# controlnode.net
KiCad netlist of a schematic drawn in EAGLE
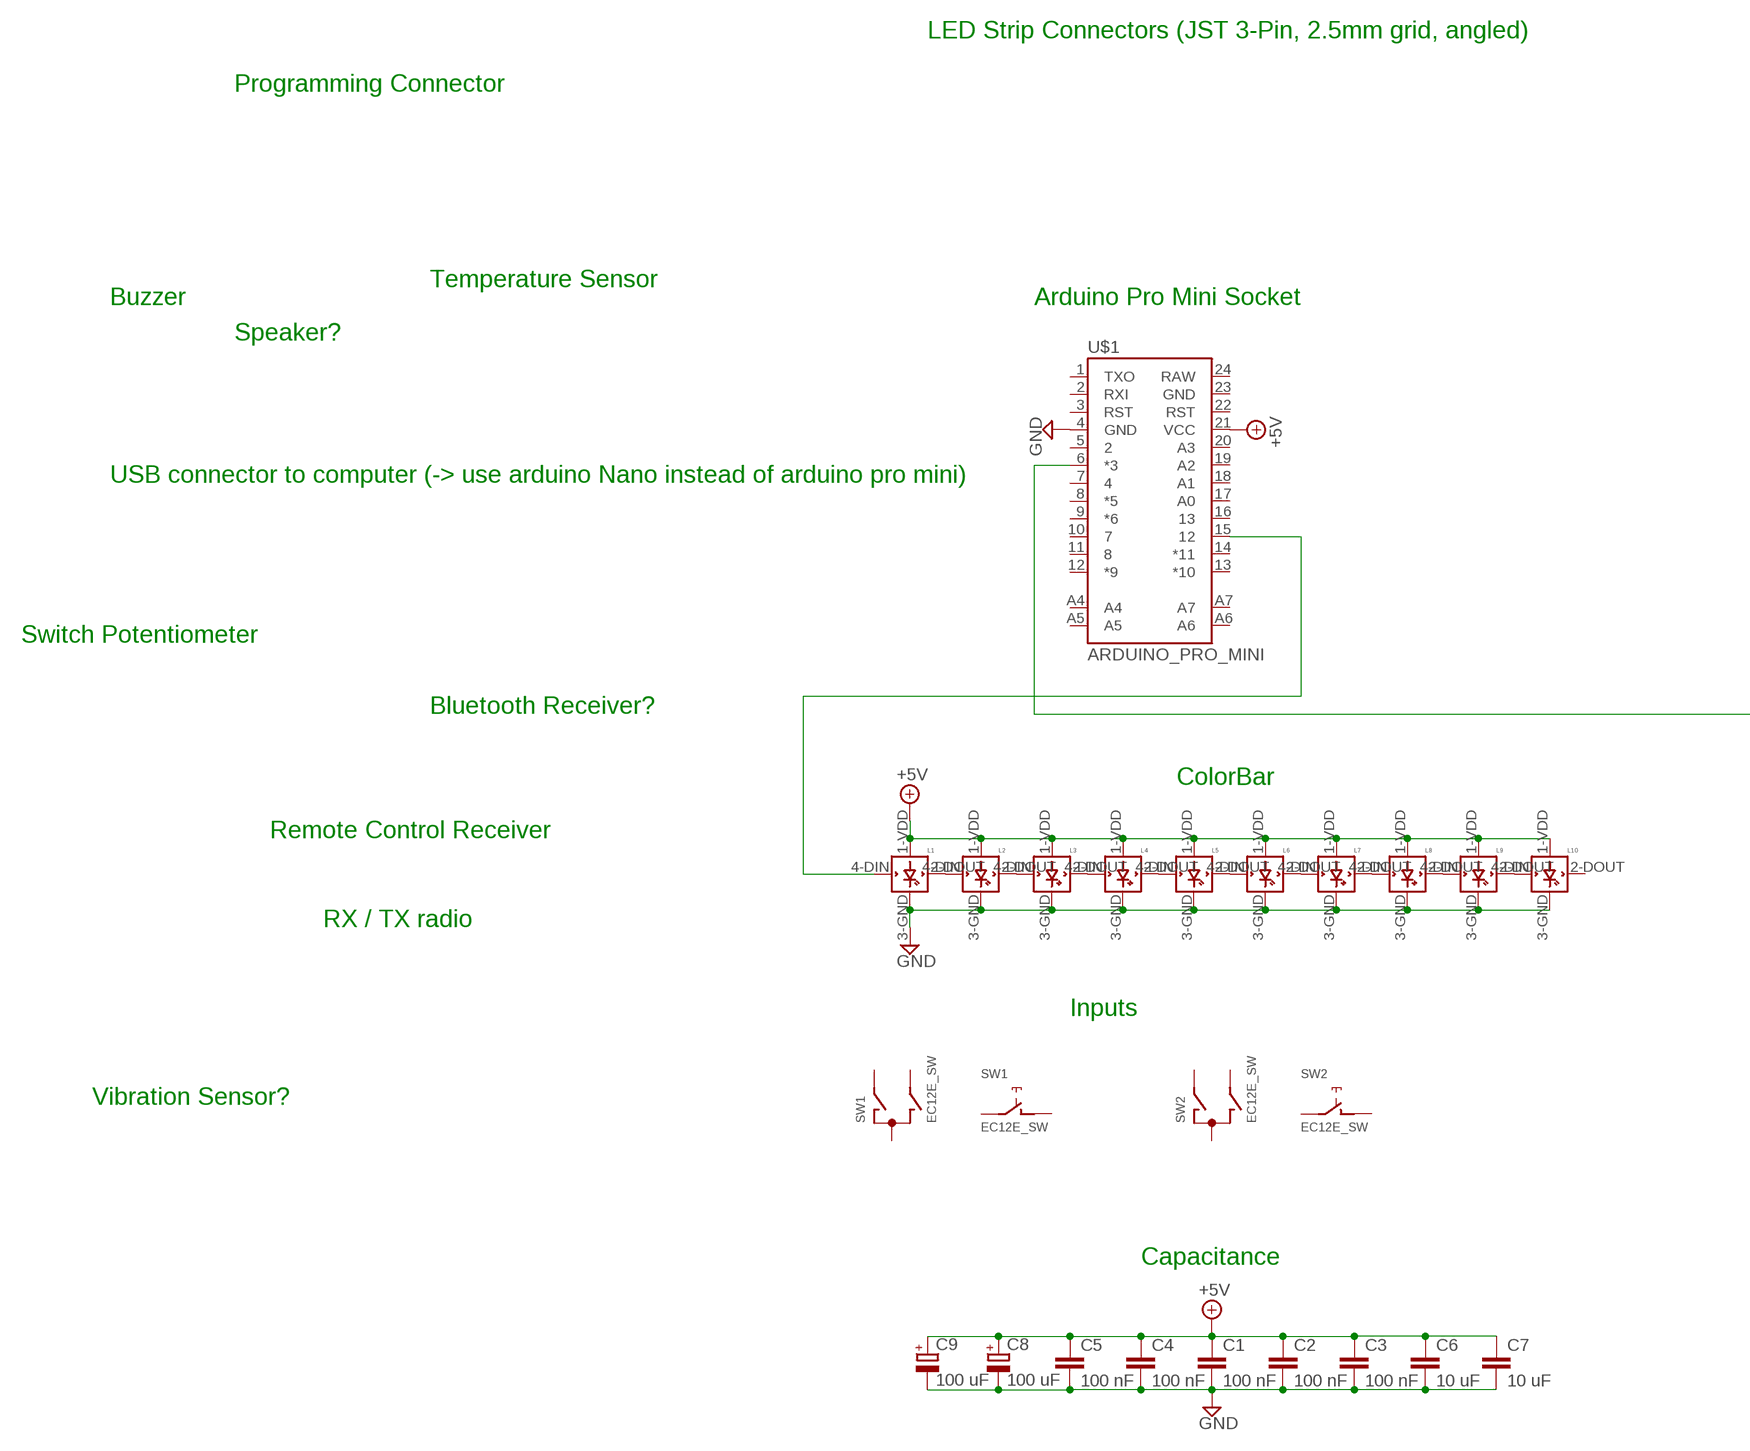
[diagram p0: schematic, sheet 1, part 1 of 2]
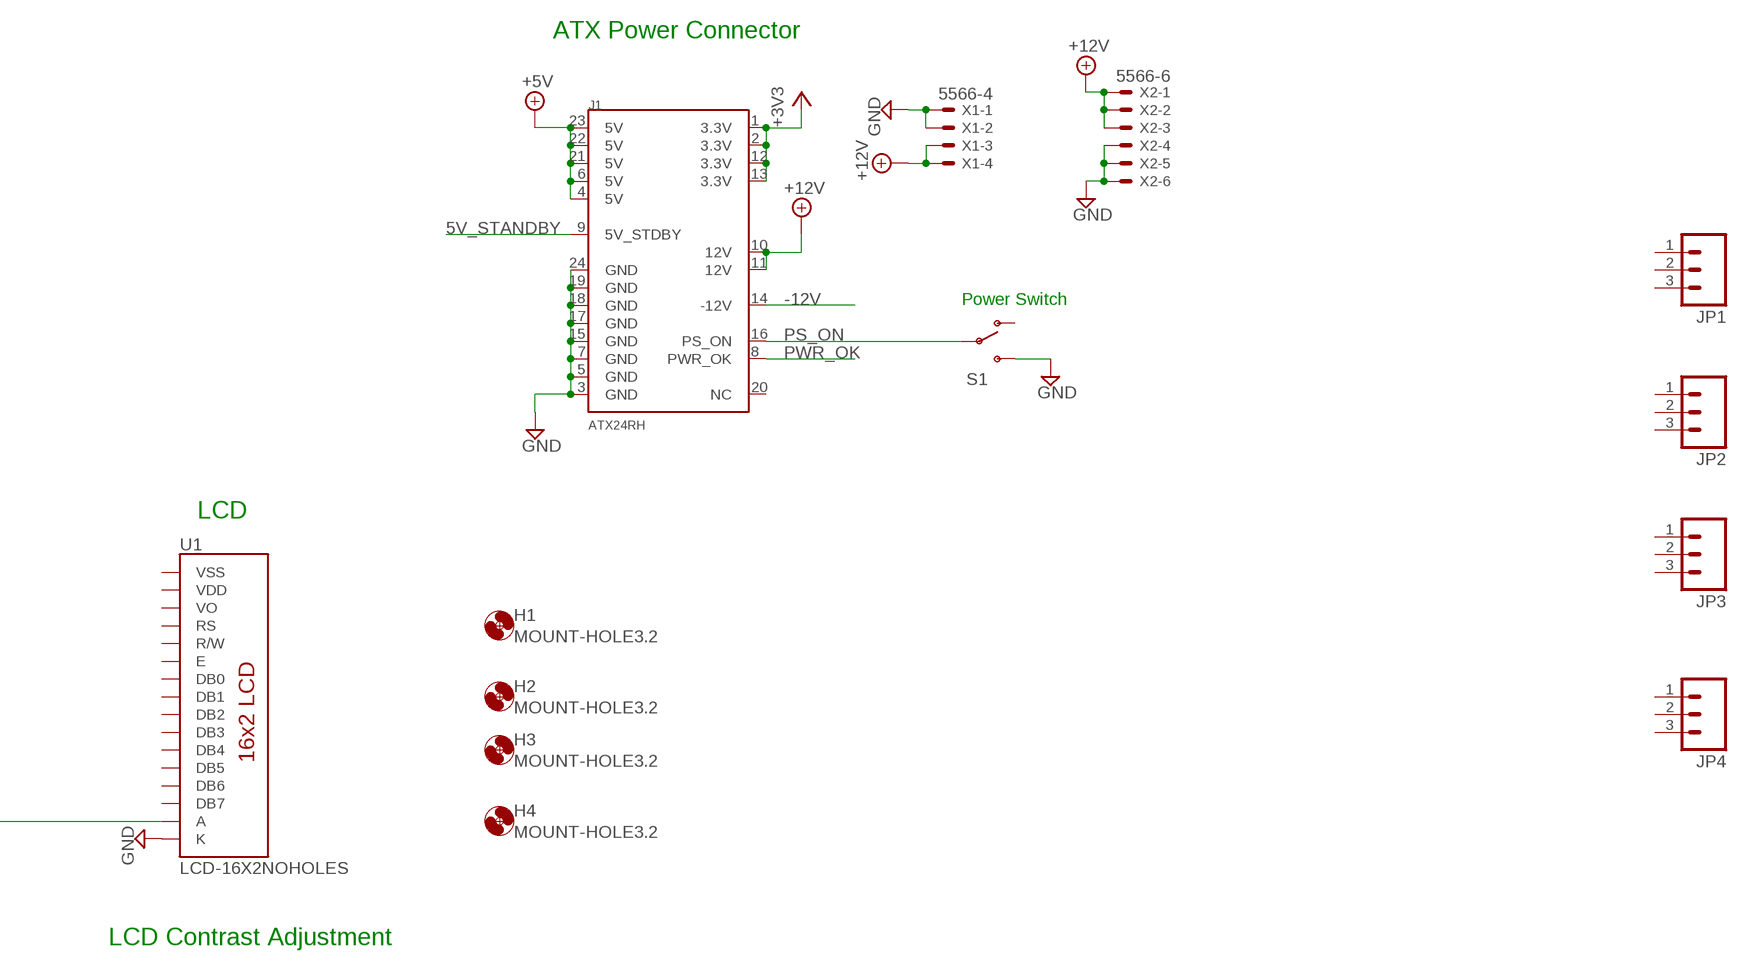
[diagram p1: schematic, sheet 1, part 2 of 2]

(export (version "E")
  (design (tool "Eeschema 10.0.6"))
  (components
    (comp (ref "C1")
      (value "100 nF")
      (footprint "eagle-import:C0805")
      (libsource (lib "eagle-import") (part "C-EUC0805"))
    )
    (comp (ref "C2")
      (value "100 nF")
      (footprint "eagle-import:C0805")
      (libsource (lib "eagle-import") (part "C-EUC0805"))
    )
    (comp (ref "C3")
      (value "100 nF")
      (footprint "eagle-import:C0805")
      (libsource (lib "eagle-import") (part "C-EUC0805"))
    )
    (comp (ref "C4")
      (value "100 nF")
      (footprint "eagle-import:C0805")
      (libsource (lib "eagle-import") (part "C-EUC0805"))
    )
    (comp (ref "C5")
      (value "100 nF")
      (footprint "eagle-import:C0805")
      (libsource (lib "eagle-import") (part "C-EUC0805"))
    )
    (comp (ref "C6")
      (value "10 uF")
      (footprint "eagle-import:C1206")
      (libsource (lib "eagle-import") (part "C-EUC1206"))
    )
    (comp (ref "C7")
      (value "10 uF")
      (footprint "eagle-import:C1206")
      (libsource (lib "eagle-import") (part "C-EUC1206"))
    )
    (comp (ref "C8")
      (value "100 uF")
      (footprint "eagle-import:E3,5-10")
      (libsource (lib "eagle-import") (part "CPOL-EUE3.5-10"))
    )
    (comp (ref "C9")
      (value "100 uF")
      (footprint "eagle-import:E3,5-10")
      (libsource (lib "eagle-import") (part "CPOL-EUE3.5-10"))
    )
    (comp (ref "H1")
      (value "MOUNT-HOLE3.2")
      (footprint "eagle-import:3,2")
      (libsource (lib "eagle-import") (part "MOUNT-HOLE3.2"))
    )
    (comp (ref "H2")
      (value "MOUNT-HOLE3.2")
      (footprint "eagle-import:3,2")
      (libsource (lib "eagle-import") (part "MOUNT-HOLE3.2"))
    )
    (comp (ref "H3")
      (value "MOUNT-HOLE3.2")
      (footprint "eagle-import:3,2")
      (libsource (lib "eagle-import") (part "MOUNT-HOLE3.2"))
    )
    (comp (ref "H4")
      (value "MOUNT-HOLE3.2")
      (footprint "eagle-import:3,2")
      (libsource (lib "eagle-import") (part "MOUNT-HOLE3.2"))
    )
    (comp (ref "J1")
      (value "ATX24RH")
      (footprint "eagle-import:ATX24_RIGHT_ANGLE")
      (libsource (lib "eagle-import") (part "ATX24RH"))
    )
    (comp (ref "JP1")
      (value "M03-SCREW-5MM")
      (footprint "eagle-import:SCREWTERMINAL-5MM-3")
      (libsource (lib "eagle-import") (part "M03-SCREW-5MM"))
    )
    (comp (ref "JP2")
      (value "M03-SCREW-5MM")
      (footprint "eagle-import:SCREWTERMINAL-5MM-3")
      (libsource (lib "eagle-import") (part "M03-SCREW-5MM"))
    )
    (comp (ref "JP3")
      (value "M03-SCREW-5MM")
      (footprint "eagle-import:SCREWTERMINAL-5MM-3")
      (libsource (lib "eagle-import") (part "M03-SCREW-5MM"))
    )
    (comp (ref "JP4")
      (value "M03-SCREW-5MM")
      (footprint "eagle-import:SCREWTERMINAL-5MM-3")
      (libsource (lib "eagle-import") (part "M03-SCREW-5MM"))
    )
    (comp (ref "L1")
      (value "WS2812B")
      (footprint "eagle-import:WS2812B")
      (libsource (lib "eagle-import") (part "WS2812B"))
    )
    (comp (ref "L2")
      (value "WS2812B")
      (footprint "eagle-import:WS2812B")
      (libsource (lib "eagle-import") (part "WS2812B"))
    )
    (comp (ref "L3")
      (value "WS2812B")
      (footprint "eagle-import:WS2812B")
      (libsource (lib "eagle-import") (part "WS2812B"))
    )
    (comp (ref "L4")
      (value "WS2812B")
      (footprint "eagle-import:WS2812B")
      (libsource (lib "eagle-import") (part "WS2812B"))
    )
    (comp (ref "L5")
      (value "WS2812B")
      (footprint "eagle-import:WS2812B")
      (libsource (lib "eagle-import") (part "WS2812B"))
    )
    (comp (ref "L6")
      (value "WS2812B")
      (footprint "eagle-import:WS2812B")
      (libsource (lib "eagle-import") (part "WS2812B"))
    )
    (comp (ref "L7")
      (value "WS2812B")
      (footprint "eagle-import:WS2812B")
      (libsource (lib "eagle-import") (part "WS2812B"))
    )
    (comp (ref "L8")
      (value "WS2812B")
      (footprint "eagle-import:WS2812B")
      (libsource (lib "eagle-import") (part "WS2812B"))
    )
    (comp (ref "L9")
      (value "WS2812B")
      (footprint "eagle-import:WS2812B")
      (libsource (lib "eagle-import") (part "WS2812B"))
    )
    (comp (ref "L10")
      (value "WS2812B")
      (footprint "eagle-import:WS2812B")
      (libsource (lib "eagle-import") (part "WS2812B"))
    )
    (comp (ref "S1")
      (value "SWITCH-SPSTPTH")
      (footprint "eagle-import:SWITCH-SPDT")
      (libsource (lib "eagle-import") (part "SWITCH-SPSTPTH"))
    )
    (comp (ref "SW1")
      (value "EC12E_SW")
      (footprint "eagle-import:ALPS_EC12E_SW")
      (fields (field (name "MPN") "EC12E2424407"))
      (libsource (lib "eagle-import") (part "EC12E_SW"))
    )
    (comp (ref "SW2")
      (value "EC12E_SW")
      (footprint "eagle-import:ALPS_EC12E_SW")
      (fields (field (name "MPN") "EC12E2424407"))
      (libsource (lib "eagle-import") (part "EC12E_SW"))
    )
    (comp (ref "U$1")
      (value "ARDUINO_PRO_MINI")
      (footprint "eagle-import:ARDUINO_PRO_MINI")
      (libsource (lib "eagle-import") (part "ARDUINO_PRO_MINI"))
    )
    (comp (ref "U1")
      (value "LCD-16X2NOHOLES")
      (footprint "eagle-import:LCD-16X2_NOHOLES")
      (libsource (lib "eagle-import") (part "LCD-16X2NOHOLES"))
    )
    (comp (ref "X1")
      (value "5566-4")
      (footprint "eagle-import:5566-4")
      (libsource (lib "eagle-import") (part "5566-4"))
    )
    (comp (ref "X2")
      (value "5566-6")
      (footprint "eagle-import:5566-6")
      (fields (field (name "MPN") "95566-61002"))
      (libsource (lib "eagle-import") (part "5566-6"))
    )
  )
  (nets
    (net (code "1") (name "+3V3") (class "Default")
      (node (ref "J1") (pin "1") (pinfunction "3.3V_1") (pintype "bidirectional"))
      (node (ref "J1") (pin "12") (pinfunction "3.3V_12") (pintype "bidirectional"))
      (node (ref "J1") (pin "13") (pinfunction "3.3V_13") (pintype "bidirectional"))
      (node (ref "J1") (pin "2") (pinfunction "3.3V_2") (pintype "bidirectional"))
    )
    (net (code "2") (name "+5V") (class "Default")
      (node (ref "C1") (pin "1") (pinfunction "1_1") (pintype "passive"))
      (node (ref "C2") (pin "1") (pinfunction "1_1") (pintype "passive"))
      (node (ref "C3") (pin "1") (pinfunction "1_1") (pintype "passive"))
      (node (ref "C4") (pin "1") (pinfunction "1_1") (pintype "passive"))
      (node (ref "C5") (pin "1") (pinfunction "1_1") (pintype "passive"))
      (node (ref "C6") (pin "1") (pinfunction "1_1") (pintype "passive"))
      (node (ref "C7") (pin "1") (pinfunction "1_1") (pintype "passive"))
      (node (ref "C8") (pin "+") (pinfunction "+_+") (pintype "passive"))
      (node (ref "C9") (pin "+") (pinfunction "+_+") (pintype "passive"))
      (node (ref "J1") (pin "21") (pinfunction "5V_21") (pintype "bidirectional"))
      (node (ref "J1") (pin "22") (pinfunction "5V_22") (pintype "bidirectional"))
      (node (ref "J1") (pin "23") (pinfunction "5V_23") (pintype "bidirectional"))
      (node (ref "J1") (pin "4") (pinfunction "5V_4") (pintype "bidirectional"))
      (node (ref "J1") (pin "6") (pinfunction "5V_6") (pintype "bidirectional"))
      (node (ref "L1") (pin "1-VDD") (pinfunction "VDD_1-VDD") (pintype "bidirectional"))
      (node (ref "L10") (pin "1-VDD") (pinfunction "VDD_1-VDD") (pintype "bidirectional"))
      (node (ref "L2") (pin "1-VDD") (pinfunction "VDD_1-VDD") (pintype "bidirectional"))
      (node (ref "L3") (pin "1-VDD") (pinfunction "VDD_1-VDD") (pintype "bidirectional"))
      (node (ref "L4") (pin "1-VDD") (pinfunction "VDD_1-VDD") (pintype "bidirectional"))
      (node (ref "L5") (pin "1-VDD") (pinfunction "VDD_1-VDD") (pintype "bidirectional"))
      (node (ref "L6") (pin "1-VDD") (pinfunction "VDD_1-VDD") (pintype "bidirectional"))
      (node (ref "L7") (pin "1-VDD") (pinfunction "VDD_1-VDD") (pintype "bidirectional"))
      (node (ref "L8") (pin "1-VDD") (pinfunction "VDD_1-VDD") (pintype "bidirectional"))
      (node (ref "L9") (pin "1-VDD") (pinfunction "VDD_1-VDD") (pintype "bidirectional"))
      (node (ref "U$1") (pin "21") (pinfunction "VCC_21") (pintype "bidirectional"))
    )
    (net (code "3") (name "+12V") (class "Default")
      (node (ref "J1") (pin "10") (pinfunction "12V_10") (pintype "bidirectional"))
      (node (ref "J1") (pin "11") (pinfunction "12V_11") (pintype "bidirectional"))
      (node (ref "X1") (pin "3") (pinfunction "S_3") (pintype "passive"))
      (node (ref "X1") (pin "4") (pinfunction "S_4") (pintype "passive"))
      (node (ref "X2") (pin "1") (pinfunction "S_1") (pintype "passive"))
      (node (ref "X2") (pin "2") (pinfunction "S_2") (pintype "passive"))
      (node (ref "X2") (pin "3") (pinfunction "S_3") (pintype "passive"))
    )
    (net (code "4") (name "/-12V") (class "Default")
      (node (ref "J1") (pin "14") (pinfunction "-12V_14") (pintype "bidirectional"))
    )
    (net (code "5") (name "/5V_STANDBY") (class "Default")
      (node (ref "J1") (pin "9") (pinfunction "5V_STDBY_9") (pintype "bidirectional"))
    )
    (net (code "6") (name "/PS_ON") (class "Default")
      (node (ref "J1") (pin "16") (pinfunction "PS_ON_16") (pintype "bidirectional"))
      (node (ref "S1") (pin "2") (pinfunction "P_2") (pintype "passive"))
    )
    (net (code "7") (name "/PWR_OK") (class "Default")
      (node (ref "J1") (pin "8") (pinfunction "PWR_OK_8") (pintype "bidirectional"))
    )
    (net (code "8") (name "/VDD") (class "Default")
      (node (ref "U1") (pin "2") (pinfunction "VDD_2") (pintype "power_in"))
    )
    (net (code "9") (name "/VSS") (class "Default")
      (node (ref "U1") (pin "1") (pinfunction "VSS_1") (pintype "power_in"))
    )
    (net (code "10") (name "GND") (class "Default")
      (node (ref "C1") (pin "2") (pinfunction "2_2") (pintype "passive"))
      (node (ref "C2") (pin "2") (pinfunction "2_2") (pintype "passive"))
      (node (ref "C3") (pin "2") (pinfunction "2_2") (pintype "passive"))
      (node (ref "C4") (pin "2") (pinfunction "2_2") (pintype "passive"))
      (node (ref "C5") (pin "2") (pinfunction "2_2") (pintype "passive"))
      (node (ref "C6") (pin "2") (pinfunction "2_2") (pintype "passive"))
      (node (ref "C7") (pin "2") (pinfunction "2_2") (pintype "passive"))
      (node (ref "C8") (pin "-") (pinfunction "-_-") (pintype "passive"))
      (node (ref "C9") (pin "-") (pinfunction "-_-") (pintype "passive"))
      (node (ref "J1") (pin "15") (pinfunction "GND_15") (pintype "bidirectional"))
      (node (ref "J1") (pin "17") (pinfunction "GND_17") (pintype "bidirectional"))
      (node (ref "J1") (pin "18") (pinfunction "GND_18") (pintype "bidirectional"))
      (node (ref "J1") (pin "19") (pinfunction "GND_19") (pintype "bidirectional"))
      (node (ref "J1") (pin "24") (pinfunction "GND_24") (pintype "bidirectional"))
      (node (ref "J1") (pin "3") (pinfunction "GND_3") (pintype "bidirectional"))
      (node (ref "J1") (pin "5") (pinfunction "GND_5") (pintype "bidirectional"))
      (node (ref "J1") (pin "7") (pinfunction "GND_7") (pintype "bidirectional"))
      (node (ref "L1") (pin "3-GND") (pinfunction "GND_3-GND") (pintype "bidirectional"))
      (node (ref "L10") (pin "3-GND") (pinfunction "GND_3-GND") (pintype "bidirectional"))
      (node (ref "L2") (pin "3-GND") (pinfunction "GND_3-GND") (pintype "bidirectional"))
      (node (ref "L3") (pin "3-GND") (pinfunction "GND_3-GND") (pintype "bidirectional"))
      (node (ref "L4") (pin "3-GND") (pinfunction "GND_3-GND") (pintype "bidirectional"))
      (node (ref "L5") (pin "3-GND") (pinfunction "GND_3-GND") (pintype "bidirectional"))
      (node (ref "L6") (pin "3-GND") (pinfunction "GND_3-GND") (pintype "bidirectional"))
      (node (ref "L7") (pin "3-GND") (pinfunction "GND_3-GND") (pintype "bidirectional"))
      (node (ref "L8") (pin "3-GND") (pinfunction "GND_3-GND") (pintype "bidirectional"))
      (node (ref "L9") (pin "3-GND") (pinfunction "GND_3-GND") (pintype "bidirectional"))
      (node (ref "S1") (pin "3") (pinfunction "S_3") (pintype "passive"))
      (node (ref "U$1") (pin "4") (pinfunction "GND_4") (pintype "bidirectional"))
      (node (ref "U1") (pin "16") (pinfunction "K_16") (pintype "power_in"))
      (node (ref "X1") (pin "1") (pinfunction "S_1") (pintype "passive"))
      (node (ref "X1") (pin "2") (pinfunction "S_2") (pintype "passive"))
      (node (ref "X2") (pin "4") (pinfunction "S_4") (pintype "passive"))
      (node (ref "X2") (pin "5") (pinfunction "S_5") (pintype "passive"))
      (node (ref "X2") (pin "6") (pinfunction "S_6") (pintype "passive"))
    )
    (net (code "11") (name "Net-(L1-DIN)") (class "Default")
      (node (ref "L1") (pin "4-DIN") (pinfunction "DIN_4-DIN") (pintype "input"))
      (node (ref "U$1") (pin "15") (pinfunction "12_15") (pintype "bidirectional"))
    )
    (net (code "12") (name "Net-(L1-DOUT)") (class "Default")
      (node (ref "L1") (pin "2-DOUT") (pinfunction "DOUT_2-DOUT") (pintype "output"))
      (node (ref "L2") (pin "4-DIN") (pinfunction "DIN_4-DIN") (pintype "input"))
    )
    (net (code "13") (name "Net-(L2-DOUT)") (class "Default")
      (node (ref "L2") (pin "2-DOUT") (pinfunction "DOUT_2-DOUT") (pintype "output"))
      (node (ref "L3") (pin "4-DIN") (pinfunction "DIN_4-DIN") (pintype "input"))
    )
    (net (code "14") (name "Net-(L3-DOUT)") (class "Default")
      (node (ref "L3") (pin "2-DOUT") (pinfunction "DOUT_2-DOUT") (pintype "output"))
      (node (ref "L4") (pin "4-DIN") (pinfunction "DIN_4-DIN") (pintype "input"))
    )
    (net (code "15") (name "Net-(L4-DOUT)") (class "Default")
      (node (ref "L4") (pin "2-DOUT") (pinfunction "DOUT_2-DOUT") (pintype "output"))
      (node (ref "L5") (pin "4-DIN") (pinfunction "DIN_4-DIN") (pintype "input"))
    )
    (net (code "16") (name "Net-(L5-DOUT)") (class "Default")
      (node (ref "L5") (pin "2-DOUT") (pinfunction "DOUT_2-DOUT") (pintype "output"))
      (node (ref "L6") (pin "4-DIN") (pinfunction "DIN_4-DIN") (pintype "input"))
    )
    (net (code "17") (name "Net-(L6-DOUT)") (class "Default")
      (node (ref "L6") (pin "2-DOUT") (pinfunction "DOUT_2-DOUT") (pintype "output"))
      (node (ref "L7") (pin "4-DIN") (pinfunction "DIN_4-DIN") (pintype "input"))
    )
    (net (code "18") (name "Net-(L7-DOUT)") (class "Default")
      (node (ref "L7") (pin "2-DOUT") (pinfunction "DOUT_2-DOUT") (pintype "output"))
      (node (ref "L8") (pin "4-DIN") (pinfunction "DIN_4-DIN") (pintype "input"))
    )
    (net (code "19") (name "Net-(L8-DOUT)") (class "Default")
      (node (ref "L8") (pin "2-DOUT") (pinfunction "DOUT_2-DOUT") (pintype "output"))
      (node (ref "L9") (pin "4-DIN") (pinfunction "DIN_4-DIN") (pintype "input"))
    )
    (net (code "20") (name "Net-(L10-DIN)") (class "Default")
      (node (ref "L10") (pin "4-DIN") (pinfunction "DIN_4-DIN") (pintype "input"))
      (node (ref "L9") (pin "2-DOUT") (pinfunction "DOUT_2-DOUT") (pintype "output"))
    )
    (net (code "21") (name "Net-(U$1-*3)") (class "Default")
      (node (ref "U$1") (pin "6") (pinfunction "*3_6") (pintype "bidirectional"))
      (node (ref "U1") (pin "15") (pinfunction "A_15") (pintype "power_in"))
    )
    (net (code "22") (name "unconnected-(J1-NC-Pad20)") (class "Default")
      (node (ref "J1") (pin "20") (pinfunction "NC_20") (pintype "bidirectional"))
    )
    (net (code "23") (name "unconnected-(JP1-Pad1)") (class "Default")
      (node (ref "JP1") (pin "1") (pinfunction "1_1") (pintype "passive"))
    )
    (net (code "24") (name "unconnected-(JP1-Pad2)") (class "Default")
      (node (ref "JP1") (pin "2") (pinfunction "2_2") (pintype "passive"))
    )
    (net (code "25") (name "unconnected-(JP1-Pad3)") (class "Default")
      (node (ref "JP1") (pin "3") (pinfunction "3_3") (pintype "passive"))
    )
    (net (code "26") (name "unconnected-(JP2-Pad1)") (class "Default")
      (node (ref "JP2") (pin "1") (pinfunction "1_1") (pintype "passive"))
    )
    (net (code "27") (name "unconnected-(JP2-Pad2)") (class "Default")
      (node (ref "JP2") (pin "2") (pinfunction "2_2") (pintype "passive"))
    )
    (net (code "28") (name "unconnected-(JP2-Pad3)") (class "Default")
      (node (ref "JP2") (pin "3") (pinfunction "3_3") (pintype "passive"))
    )
    (net (code "29") (name "unconnected-(JP3-Pad1)") (class "Default")
      (node (ref "JP3") (pin "1") (pinfunction "1_1") (pintype "passive"))
    )
    (net (code "30") (name "unconnected-(JP3-Pad2)") (class "Default")
      (node (ref "JP3") (pin "2") (pinfunction "2_2") (pintype "passive"))
    )
    (net (code "31") (name "unconnected-(JP3-Pad3)") (class "Default")
      (node (ref "JP3") (pin "3") (pinfunction "3_3") (pintype "passive"))
    )
    (net (code "32") (name "unconnected-(JP4-Pad1)") (class "Default")
      (node (ref "JP4") (pin "1") (pinfunction "1_1") (pintype "passive"))
    )
    (net (code "33") (name "unconnected-(JP4-Pad2)") (class "Default")
      (node (ref "JP4") (pin "2") (pinfunction "2_2") (pintype "passive"))
    )
    (net (code "34") (name "unconnected-(JP4-Pad3)") (class "Default")
      (node (ref "JP4") (pin "3") (pinfunction "3_3") (pintype "passive"))
    )
    (net (code "35") (name "unconnected-(L10-DOUT-Pad2-DOUT)") (class "Default")
      (node (ref "L10") (pin "2-DOUT") (pinfunction "DOUT_2-DOUT") (pintype "output"))
    )
    (net (code "36") (name "unconnected-(S1-O-Pad1)") (class "Default")
      (node (ref "S1") (pin "1") (pinfunction "O_1") (pintype "passive"))
    )
    (net (code "37") (name "unconnected-(SW1-PadA)") (class "Default")
      (node (ref "SW1") (pin "A") (pinfunction "A_A") (pintype "passive"))
    )
    (net (code "38") (name "unconnected-(SW1-PadB)") (class "Default")
      (node (ref "SW1") (pin "B") (pinfunction "B_B") (pintype "passive"))
    )
    (net (code "39") (name "unconnected-(SW1-PadC)") (class "Default")
      (node (ref "SW1") (pin "C") (pinfunction "C_C") (pintype "passive"))
    )
    (net (code "40") (name "unconnected-(SW1B-1-PadD)") (class "Default")
      (node (ref "SW1") (pin "D") (pinfunction "1_D") (pintype "passive"))
    )
    (net (code "41") (name "unconnected-(SW1B-2-PadE)") (class "Default")
      (node (ref "SW1") (pin "E") (pinfunction "2_E") (pintype "passive"))
    )
    (net (code "42") (name "unconnected-(SW2-PadA)") (class "Default")
      (node (ref "SW2") (pin "A") (pinfunction "A_A") (pintype "passive"))
    )
    (net (code "43") (name "unconnected-(SW2-PadB)") (class "Default")
      (node (ref "SW2") (pin "B") (pinfunction "B_B") (pintype "passive"))
    )
    (net (code "44") (name "unconnected-(SW2-PadC)") (class "Default")
      (node (ref "SW2") (pin "C") (pinfunction "C_C") (pintype "passive"))
    )
    (net (code "45") (name "unconnected-(SW2B-1-PadD)") (class "Default")
      (node (ref "SW2") (pin "D") (pinfunction "1_D") (pintype "passive"))
    )
    (net (code "46") (name "unconnected-(SW2B-2-PadE)") (class "Default")
      (node (ref "SW2") (pin "E") (pinfunction "2_E") (pintype "passive"))
    )
    (net (code "47") (name "unconnected-(U$1-*5-Pad8)") (class "Default")
      (node (ref "U$1") (pin "8") (pinfunction "*5_8") (pintype "bidirectional"))
    )
    (net (code "48") (name "unconnected-(U$1-*6-Pad9)") (class "Default")
      (node (ref "U$1") (pin "9") (pinfunction "*6_9") (pintype "bidirectional"))
    )
    (net (code "49") (name "unconnected-(U$1-*9-Pad12)") (class "Default")
      (node (ref "U$1") (pin "12") (pinfunction "*9_12") (pintype "bidirectional"))
    )
    (net (code "50") (name "unconnected-(U$1-*10-Pad13)") (class "Default")
      (node (ref "U$1") (pin "13") (pinfunction "*10_13") (pintype "bidirectional"))
    )
    (net (code "51") (name "unconnected-(U$1-*11-Pad14)") (class "Default")
      (node (ref "U$1") (pin "14") (pinfunction "*11_14") (pintype "bidirectional"))
    )
    (net (code "52") (name "unconnected-(U$1-2-Pad5)") (class "Default")
      (node (ref "U$1") (pin "5") (pinfunction "2_5") (pintype "bidirectional"))
    )
    (net (code "53") (name "unconnected-(U$1-4-Pad7)") (class "Default")
      (node (ref "U$1") (pin "7") (pinfunction "4_7") (pintype "bidirectional"))
    )
    (net (code "54") (name "unconnected-(U$1-7-Pad10)") (class "Default")
      (node (ref "U$1") (pin "10") (pinfunction "7_10") (pintype "bidirectional"))
    )
    (net (code "55") (name "unconnected-(U$1-8-Pad11)") (class "Default")
      (node (ref "U$1") (pin "11") (pinfunction "8_11") (pintype "bidirectional"))
    )
    (net (code "56") (name "unconnected-(U$1-13-Pad16)") (class "Default")
      (node (ref "U$1") (pin "16") (pinfunction "13_16") (pintype "bidirectional"))
    )
    (net (code "57") (name "unconnected-(U$1-A0-Pad17)") (class "Default")
      (node (ref "U$1") (pin "17") (pinfunction "A0_17") (pintype "bidirectional"))
    )
    (net (code "58") (name "unconnected-(U$1-A1-Pad18)") (class "Default")
      (node (ref "U$1") (pin "18") (pinfunction "A1_18") (pintype "bidirectional"))
    )
    (net (code "59") (name "unconnected-(U$1-A2-Pad19)") (class "Default")
      (node (ref "U$1") (pin "19") (pinfunction "A2_19") (pintype "bidirectional"))
    )
    (net (code "60") (name "unconnected-(U$1-A3-Pad20)") (class "Default")
      (node (ref "U$1") (pin "20") (pinfunction "A3_20") (pintype "bidirectional"))
    )
    (net (code "61") (name "unconnected-(U$1-GND-Pad23)") (class "Default")
      (node (ref "U$1") (pin "23") (pinfunction "GND_23") (pintype "bidirectional"))
    )
    (net (code "62") (name "unconnected-(U$1-PadA4)") (class "Default")
      (node (ref "U$1") (pin "A4") (pinfunction "A4_A4") (pintype "bidirectional"))
    )
    (net (code "63") (name "unconnected-(U$1-PadA5)") (class "Default")
      (node (ref "U$1") (pin "A5") (pinfunction "A5_A5") (pintype "bidirectional"))
    )
    (net (code "64") (name "unconnected-(U$1-PadA6)") (class "Default")
      (node (ref "U$1") (pin "A6") (pinfunction "A6_A6") (pintype "bidirectional"))
    )
    (net (code "65") (name "unconnected-(U$1-PadA7)") (class "Default")
      (node (ref "U$1") (pin "A7") (pinfunction "A7_A7") (pintype "bidirectional"))
    )
    (net (code "66") (name "unconnected-(U$1-RAW-Pad24)") (class "Default")
      (node (ref "U$1") (pin "24") (pinfunction "RAW_24") (pintype "bidirectional"))
    )
    (net (code "67") (name "unconnected-(U$1-RST-Pad3)") (class "Default")
      (node (ref "U$1") (pin "3") (pinfunction "RST_3") (pintype "bidirectional"))
    )
    (net (code "68") (name "unconnected-(U$1-RST-Pad22)") (class "Default")
      (node (ref "U$1") (pin "22") (pinfunction "RST_22") (pintype "bidirectional"))
    )
    (net (code "69") (name "unconnected-(U$1-RXI-Pad2)") (class "Default")
      (node (ref "U$1") (pin "2") (pinfunction "RXI_2") (pintype "bidirectional"))
    )
    (net (code "70") (name "unconnected-(U$1-TXO-Pad1)") (class "Default")
      (node (ref "U$1") (pin "1") (pinfunction "TXO_1") (pintype "bidirectional"))
    )
    (net (code "71") (name "unconnected-(U1-DB0-Pad7)") (class "Default")
      (node (ref "U1") (pin "7") (pinfunction "DB0_7") (pintype "bidirectional"))
    )
    (net (code "72") (name "unconnected-(U1-DB1-Pad8)") (class "Default")
      (node (ref "U1") (pin "8") (pinfunction "DB1_8") (pintype "bidirectional"))
    )
    (net (code "73") (name "unconnected-(U1-DB2-Pad9)") (class "Default")
      (node (ref "U1") (pin "9") (pinfunction "DB2_9") (pintype "bidirectional"))
    )
    (net (code "74") (name "unconnected-(U1-DB3-Pad10)") (class "Default")
      (node (ref "U1") (pin "10") (pinfunction "DB3_10") (pintype "bidirectional"))
    )
    (net (code "75") (name "unconnected-(U1-DB4-Pad11)") (class "Default")
      (node (ref "U1") (pin "11") (pinfunction "DB4_11") (pintype "bidirectional"))
    )
    (net (code "76") (name "unconnected-(U1-DB5-Pad12)") (class "Default")
      (node (ref "U1") (pin "12") (pinfunction "DB5_12") (pintype "bidirectional"))
    )
    (net (code "77") (name "unconnected-(U1-DB6-Pad13)") (class "Default")
      (node (ref "U1") (pin "13") (pinfunction "DB6_13") (pintype "bidirectional"))
    )
    (net (code "78") (name "unconnected-(U1-DB7-Pad14)") (class "Default")
      (node (ref "U1") (pin "14") (pinfunction "DB7_14") (pintype "bidirectional"))
    )
    (net (code "79") (name "unconnected-(U1-E-Pad6)") (class "Default")
      (node (ref "U1") (pin "6") (pinfunction "E_6") (pintype "input"))
    )
    (net (code "80") (name "unconnected-(U1-RS-Pad4)") (class "Default")
      (node (ref "U1") (pin "4") (pinfunction "RS_4") (pintype "input"))
    )
    (net (code "81") (name "unconnected-(U1-R{slash}W-Pad5)") (class "Default")
      (node (ref "U1") (pin "5") (pinfunction "R/W_5") (pintype "input"))
    )
    (net (code "82") (name "unconnected-(U1-VO-Pad3)") (class "Default")
      (node (ref "U1") (pin "3") (pinfunction "VO_3") (pintype "bidirectional"))
    )
  )
)
